# Schematic_DACPCM1780LP-filter_2.net
KiCad netlist of a schematic drawn in EAGLE
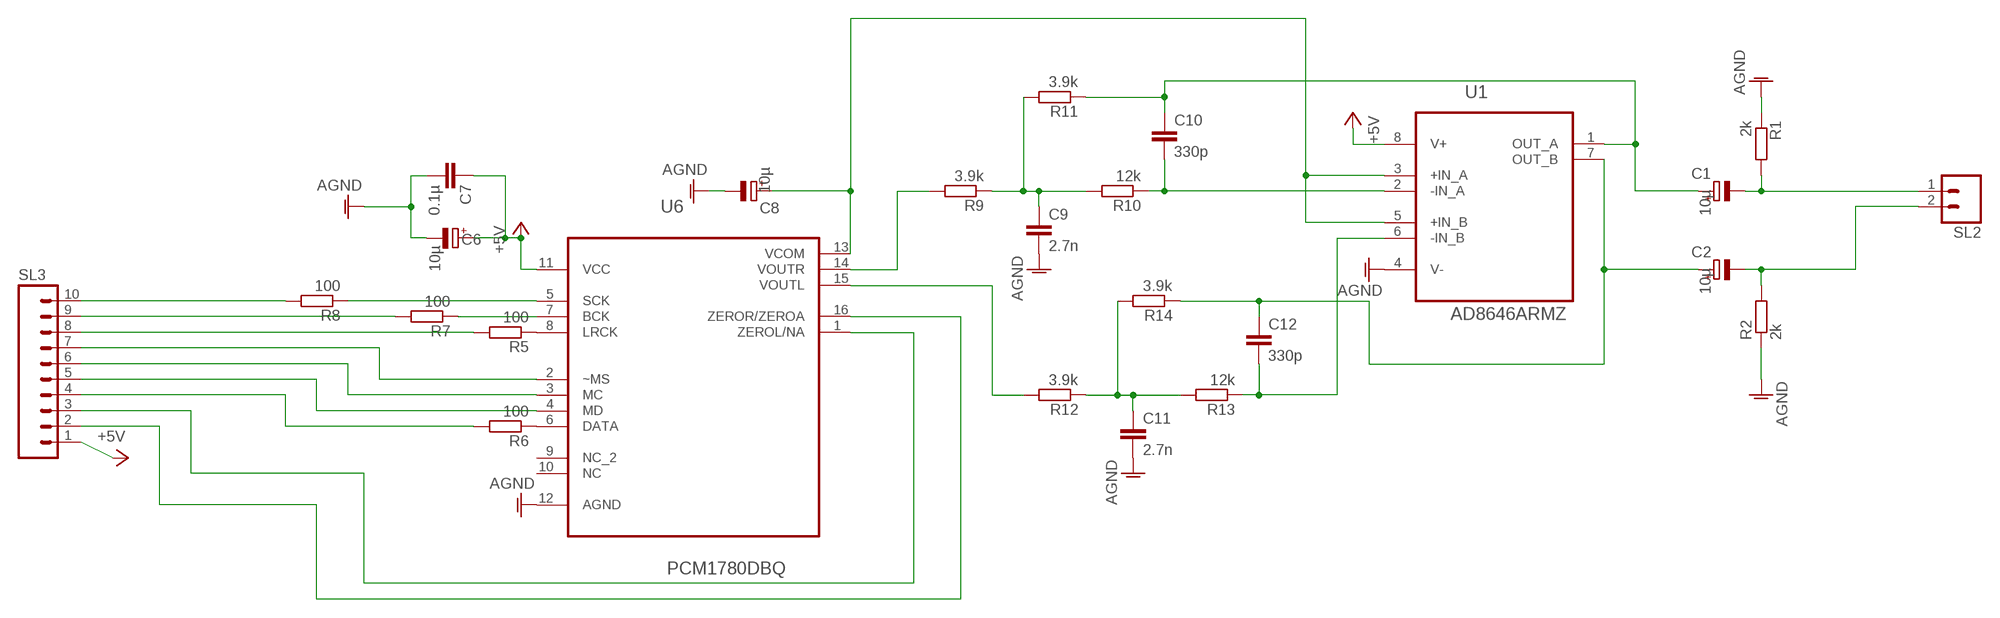
[diagram p0: schematic, sheet 1]

(export (version "E")
  (design (tool "Eeschema 10.0.6"))
  (components
    (comp (ref "C1")
      (value "10µ")
      (footprint "eagle-import:085CS_1AR")
      (libsource (lib "eagle-import") (part "CPOL-EU085CS-1AR"))
    )
    (comp (ref "C2")
      (value "10µ")
      (footprint "eagle-import:085CS_1AR")
      (libsource (lib "eagle-import") (part "CPOL-EU085CS-1AR"))
    )
    (comp (ref "C6")
      (value "10µ")
      (footprint "eagle-import:085CS_1AR")
      (libsource (lib "eagle-import") (part "CPOL-EU085CS-1AR"))
    )
    (comp (ref "C7")
      (value "0.1µ")
      (footprint "eagle-import:C0805K")
      (libsource (lib "eagle-import") (part "C-EUC0805K"))
    )
    (comp (ref "C8")
      (value "10µ")
      (footprint "eagle-import:085CS_1AR")
      (libsource (lib "eagle-import") (part "CPOL-EU085CS-1AR"))
    )
    (comp (ref "C9")
      (value "2.7n")
      (footprint "eagle-import:C0805K")
      (libsource (lib "eagle-import") (part "C-EUC0805K"))
    )
    (comp (ref "C10")
      (value "330p")
      (footprint "eagle-import:C0805K")
      (libsource (lib "eagle-import") (part "C-EUC0805K"))
    )
    (comp (ref "C11")
      (value "2.7n")
      (footprint "eagle-import:C0805K")
      (libsource (lib "eagle-import") (part "C-EUC0805K"))
    )
    (comp (ref "C12")
      (value "330p")
      (footprint "eagle-import:C0805K")
      (libsource (lib "eagle-import") (part "C-EUC0805K"))
    )
    (comp (ref "R1")
      (value "2k")
      (footprint "eagle-import:M0805")
      (libsource (lib "eagle-import") (part "R-EU_M0805"))
    )
    (comp (ref "R2")
      (value "2k")
      (footprint "eagle-import:M0805")
      (libsource (lib "eagle-import") (part "R-EU_M0805"))
    )
    (comp (ref "R5")
      (value "100")
      (footprint "eagle-import:M0805")
      (libsource (lib "eagle-import") (part "R-EU_M0805"))
    )
    (comp (ref "R6")
      (value "100")
      (footprint "eagle-import:M0805")
      (libsource (lib "eagle-import") (part "R-EU_M0805"))
    )
    (comp (ref "R7")
      (value "100")
      (footprint "eagle-import:M0805")
      (libsource (lib "eagle-import") (part "R-EU_M0805"))
    )
    (comp (ref "R8")
      (value "100")
      (footprint "eagle-import:M0805")
      (libsource (lib "eagle-import") (part "R-EU_M0805"))
    )
    (comp (ref "R9")
      (value "3.9k")
      (footprint "eagle-import:M0805")
      (libsource (lib "eagle-import") (part "R-EU_M0805"))
    )
    (comp (ref "R10")
      (value "12k")
      (footprint "eagle-import:M0805")
      (libsource (lib "eagle-import") (part "R-EU_M0805"))
    )
    (comp (ref "R11")
      (value "3.9k")
      (footprint "eagle-import:M0805")
      (libsource (lib "eagle-import") (part "R-EU_M0805"))
    )
    (comp (ref "R12")
      (value "3.9k")
      (footprint "eagle-import:M0805")
      (libsource (lib "eagle-import") (part "R-EU_M0805"))
    )
    (comp (ref "R13")
      (value "12k")
      (footprint "eagle-import:M0805")
      (libsource (lib "eagle-import") (part "R-EU_M0805"))
    )
    (comp (ref "R14")
      (value "3.9k")
      (footprint "eagle-import:M0805")
      (libsource (lib "eagle-import") (part "R-EU_M0805"))
    )
    (comp (ref "SL2")
      (value "M02")
      (footprint "eagle-import:02P")
      (libsource (lib "eagle-import") (part "M02"))
    )
    (comp (ref "SL3")
      (value "M10")
      (footprint "eagle-import:10P")
      (libsource (lib "eagle-import") (part "M10"))
    )
    (comp (ref "U1")
      (value "AD8646ARMZ")
      (footprint "eagle-import:SOP65P490X110-8N")
      (fields (field (name "MF") "Analog Devices"))
      (libsource (lib "eagle-import") (part "AD8646ARMZ"))
    )
    (comp (ref "U6")
      (value "PCM1780DBQ")
      (footprint "eagle-import:SOP63P600X175-16N")
      (fields (field (name "MF") "Texas Instruments"))
      (libsource (lib "eagle-import") (part "PCM1780DBQ"))
    )
  )
  (nets
    (net (code "1") (name "+5V") (class "Default")
      (node (ref "C6") (pin "+") (pinfunction "+_+") (pintype "passive"))
      (node (ref "C7") (pin "1") (pinfunction "1_1") (pintype "passive"))
      (node (ref "SL3") (pin "1") (pinfunction "1_1") (pintype "passive"))
      (node (ref "U1") (pin "8") (pinfunction "V+_8") (pintype "power_in"))
      (node (ref "U6") (pin "11") (pinfunction "VCC_11") (pintype "power_in"))
    )
    (net (code "2") (name "AGND") (class "Default")
      (node (ref "C11") (pin "2") (pinfunction "2_2") (pintype "passive"))
      (node (ref "C6") (pin "-") (pinfunction "-_-") (pintype "passive"))
      (node (ref "C7") (pin "2") (pinfunction "2_2") (pintype "passive"))
      (node (ref "C8") (pin "-") (pinfunction "-_-") (pintype "passive"))
      (node (ref "C9") (pin "2") (pinfunction "2_2") (pintype "passive"))
      (node (ref "R1") (pin "1") (pinfunction "1_1") (pintype "passive"))
      (node (ref "R2") (pin "1") (pinfunction "1_1") (pintype "passive"))
      (node (ref "U1") (pin "4") (pinfunction "V-_4") (pintype "power_in"))
      (node (ref "U6") (pin "12") (pinfunction "AGND_12") (pintype "passive"))
    )
    (net (code "3") (name "Net-(C1-Pad-)") (class "Default")
      (node (ref "C1") (pin "-") (pinfunction "-_-") (pintype "passive"))
      (node (ref "R1") (pin "2") (pinfunction "2_2") (pintype "passive"))
      (node (ref "SL2") (pin "1") (pinfunction "1_1") (pintype "passive"))
    )
    (net (code "4") (name "Net-(C2-Pad-)") (class "Default")
      (node (ref "C2") (pin "-") (pinfunction "-_-") (pintype "passive"))
      (node (ref "R2") (pin "2") (pinfunction "2_2") (pintype "passive"))
      (node (ref "SL2") (pin "2") (pinfunction "2_2") (pintype "passive"))
    )
    (net (code "5") (name "Net-(C9-Pad1)") (class "Default")
      (node (ref "C9") (pin "1") (pinfunction "1_1") (pintype "passive"))
      (node (ref "R10") (pin "2") (pinfunction "2_2") (pintype "passive"))
      (node (ref "R11") (pin "2") (pinfunction "2_2") (pintype "passive"))
      (node (ref "R9") (pin "1") (pinfunction "1_1") (pintype "passive"))
    )
    (net (code "6") (name "Net-(C11-Pad1)") (class "Default")
      (node (ref "C11") (pin "1") (pinfunction "1_1") (pintype "passive"))
      (node (ref "R12") (pin "1") (pinfunction "1_1") (pintype "passive"))
      (node (ref "R13") (pin "2") (pinfunction "2_2") (pintype "passive"))
      (node (ref "R14") (pin "2") (pinfunction "2_2") (pintype "passive"))
    )
    (net (code "7") (name "Net-(R5-Pad2)") (class "Default")
      (node (ref "R5") (pin "2") (pinfunction "2_2") (pintype "passive"))
      (node (ref "SL3") (pin "8") (pinfunction "8_8") (pintype "passive"))
    )
    (net (code "8") (name "Net-(R6-Pad2)") (class "Default")
      (node (ref "R6") (pin "2") (pinfunction "2_2") (pintype "passive"))
      (node (ref "SL3") (pin "4") (pinfunction "4_4") (pintype "passive"))
    )
    (net (code "9") (name "Net-(R7-Pad2)") (class "Default")
      (node (ref "R7") (pin "2") (pinfunction "2_2") (pintype "passive"))
      (node (ref "SL3") (pin "9") (pinfunction "9_9") (pintype "passive"))
    )
    (net (code "10") (name "Net-(R8-Pad2)") (class "Default")
      (node (ref "R8") (pin "2") (pinfunction "2_2") (pintype "passive"))
      (node (ref "SL3") (pin "10") (pinfunction "10_10") (pintype "passive"))
    )
    (net (code "11") (name "Net-(U1-+IN_A)") (class "Default")
      (node (ref "C8") (pin "+") (pinfunction "+_+") (pintype "passive"))
      (node (ref "U1") (pin "3") (pinfunction "+IN_A_3") (pintype "input"))
      (node (ref "U1") (pin "5") (pinfunction "+IN_B_5") (pintype "input"))
      (node (ref "U6") (pin "13") (pinfunction "VCOM_13") (pintype "passive"))
    )
    (net (code "12") (name "Net-(U1--IN_A)") (class "Default")
      (node (ref "C10") (pin "2") (pinfunction "2_2") (pintype "passive"))
      (node (ref "R10") (pin "1") (pinfunction "1_1") (pintype "passive"))
      (node (ref "U1") (pin "2") (pinfunction "-IN_A_2") (pintype "input"))
    )
    (net (code "13") (name "Net-(U1--IN_B)") (class "Default")
      (node (ref "C12") (pin "2") (pinfunction "2_2") (pintype "passive"))
      (node (ref "R13") (pin "1") (pinfunction "1_1") (pintype "passive"))
      (node (ref "U1") (pin "6") (pinfunction "-IN_B_6") (pintype "input"))
    )
    (net (code "14") (name "Net-(U1-OUT_A)") (class "Default")
      (node (ref "C1") (pin "+") (pinfunction "+_+") (pintype "passive"))
      (node (ref "C10") (pin "1") (pinfunction "1_1") (pintype "passive"))
      (node (ref "R11") (pin "1") (pinfunction "1_1") (pintype "passive"))
      (node (ref "U1") (pin "1") (pinfunction "OUT_A_1") (pintype "output"))
    )
    (net (code "15") (name "Net-(U1-OUT_B)") (class "Default")
      (node (ref "C12") (pin "1") (pinfunction "1_1") (pintype "passive"))
      (node (ref "C2") (pin "+") (pinfunction "+_+") (pintype "passive"))
      (node (ref "R14") (pin "1") (pinfunction "1_1") (pintype "passive"))
      (node (ref "U1") (pin "7") (pinfunction "OUT_B_7") (pintype "output"))
    )
    (net (code "16") (name "Net-(U6-BCK)") (class "Default")
      (node (ref "R7") (pin "1") (pinfunction "1_1") (pintype "passive"))
      (node (ref "U6") (pin "7") (pinfunction "BCK_7") (pintype "input"))
    )
    (net (code "17") (name "Net-(U6-DATA)") (class "Default")
      (node (ref "R6") (pin "1") (pinfunction "1_1") (pintype "passive"))
      (node (ref "U6") (pin "6") (pinfunction "DATA_6") (pintype "input"))
    )
    (net (code "18") (name "Net-(U6-LRCK)") (class "Default")
      (node (ref "R5") (pin "1") (pinfunction "1_1") (pintype "passive"))
      (node (ref "U6") (pin "8") (pinfunction "LRCK_8") (pintype "input"))
    )
    (net (code "19") (name "Net-(U6-MC)") (class "Default")
      (node (ref "SL3") (pin "6") (pinfunction "6_6") (pintype "passive"))
      (node (ref "U6") (pin "3") (pinfunction "MC_3") (pintype "input"))
    )
    (net (code "20") (name "Net-(U6-MD)") (class "Default")
      (node (ref "SL3") (pin "5") (pinfunction "5_5") (pintype "passive"))
      (node (ref "U6") (pin "4") (pinfunction "MD_4") (pintype "input"))
    )
    (net (code "21") (name "Net-(U6-SCK)") (class "Default")
      (node (ref "R8") (pin "1") (pinfunction "1_1") (pintype "passive"))
      (node (ref "U6") (pin "5") (pinfunction "SCK_5") (pintype "input"))
    )
    (net (code "22") (name "Net-(U6-VOUTL)") (class "Default")
      (node (ref "R12") (pin "2") (pinfunction "2_2") (pintype "passive"))
      (node (ref "U6") (pin "15") (pinfunction "VOUTL_15") (pintype "output"))
    )
    (net (code "23") (name "Net-(U6-VOUTR)") (class "Default")
      (node (ref "R9") (pin "2") (pinfunction "2_2") (pintype "passive"))
      (node (ref "U6") (pin "14") (pinfunction "VOUTR_14") (pintype "output"))
    )
    (net (code "24") (name "Net-(U6-ZEROL{slash}NA)") (class "Default")
      (node (ref "SL3") (pin "3") (pinfunction "3_3") (pintype "passive"))
      (node (ref "U6") (pin "1") (pinfunction "ZEROL/NA_1") (pintype "output"))
    )
    (net (code "25") (name "Net-(U6-ZEROR{slash}ZEROA)") (class "Default")
      (node (ref "SL3") (pin "2") (pinfunction "2_2") (pintype "passive"))
      (node (ref "U6") (pin "16") (pinfunction "ZEROR/ZEROA_16") (pintype "output"))
    )
    (net (code "26") (name "Net-(U6-~{MS})") (class "Default")
      (node (ref "SL3") (pin "7") (pinfunction "7_7") (pintype "passive"))
      (node (ref "U6") (pin "2") (pinfunction "~{MS}_2") (pintype "input"))
    )
    (net (code "27") (name "unconnected-(U6-NC-Pad10)") (class "Default")
      (node (ref "U6") (pin "10") (pinfunction "NC_10") (pintype "no_connect"))
    )
    (net (code "28") (name "unconnected-(U6-NC_2-Pad9)") (class "Default")
      (node (ref "U6") (pin "9") (pinfunction "NC_2_9") (pintype "no_connect"))
    )
  )
)
